# Sheet1.net
KiCad netlist of a schematic drawn in Altium Designer
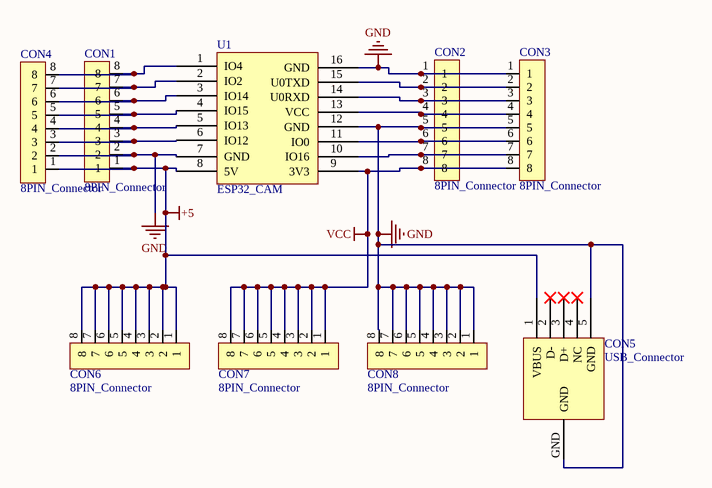
[diagram p0: Sheet1.SchDoc]

(export (version "E")
  (design (tool "Eeschema 10.0.6"))
  (components
    (comp (ref "CON1")
      (value "8PIN_Connector")
      (footprint "8PIN")
      (libsource (lib "") (part "8PIN_Connector_1"))
    )
    (comp (ref "CON2")
      (value "8PIN_Connector")
      (footprint "8PIN")
      (libsource (lib "") (part "8PIN_Connector_2"))
    )
    (comp (ref "CON3")
      (value "8PIN_Connector")
      (footprint "8PIN")
      (libsource (lib "") (part "8PIN_Connector_2"))
    )
    (comp (ref "CON4")
      (value "8PIN_Connector")
      (footprint "8PIN")
      (libsource (lib "") (part "8PIN_Connector_1"))
    )
    (comp (ref "CON5")
      (value "USB_Connector")
      (footprint "MicroUSB")
      (libsource (lib "Mylib") (part "USB_Connector"))
    )
    (comp (ref "CON6")
      (value "8PIN_Connector")
      (footprint "8PIN_2")
      (libsource (lib "Mylib") (part "8PIN_Connector"))
    )
    (comp (ref "CON7")
      (value "8PIN_Connector")
      (footprint "8PIN_2")
      (libsource (lib "Mylib") (part "8PIN_Connector"))
    )
    (comp (ref "CON8")
      (value "8PIN_Connector")
      (footprint "8PIN_2")
      (libsource (lib "Mylib") (part "8PIN_Connector"))
    )
    (comp (ref "U1")
      (value "ESP32_CAM")
      (footprint "ESPCAM_BOARD")
      (libsource (lib "Mylib") (part "ESP32_CAM"))
    )
  )
  (nets
    (net (code "1") (name "+5") (class "Default")
      (node (ref "CON1") (pin "1") (pinfunction "1_1") (pintype "passive"))
      (node (ref "CON4") (pin "1") (pinfunction "1_1") (pintype "passive"))
      (node (ref "CON5") (pin "1") (pinfunction "VBUS_1") (pintype "passive"))
      (node (ref "CON6") (pin "1") (pinfunction "1_1") (pintype "passive"))
      (node (ref "CON6") (pin "2") (pinfunction "2_2") (pintype "passive"))
      (node (ref "CON6") (pin "3") (pinfunction "3_3") (pintype "passive"))
      (node (ref "CON6") (pin "4") (pinfunction "4_4") (pintype "passive"))
      (node (ref "CON6") (pin "5") (pinfunction "5_5") (pintype "passive"))
      (node (ref "CON6") (pin "6") (pinfunction "6_6") (pintype "passive"))
      (node (ref "CON6") (pin "7") (pinfunction "7_7") (pintype "passive"))
      (node (ref "CON6") (pin "8") (pinfunction "8_8") (pintype "passive"))
      (node (ref "U1") (pin "8") (pinfunction "5V_8") (pintype "passive"))
    )
    (net (code "2") (name "GND") (class "Default")
      (node (ref "CON1") (pin "2") (pinfunction "2_2") (pintype "passive"))
      (node (ref "CON2") (pin "1") (pinfunction "1_1") (pintype "passive"))
      (node (ref "CON2") (pin "5") (pinfunction "5_5") (pintype "passive"))
      (node (ref "CON3") (pin "1") (pinfunction "1_1") (pintype "passive"))
      (node (ref "CON3") (pin "5") (pinfunction "5_5") (pintype "passive"))
      (node (ref "CON4") (pin "2") (pinfunction "2_2") (pintype "passive"))
      (node (ref "CON5") (pin "5") (pinfunction "GND_5") (pintype "passive"))
      (node (ref "CON5") (pin "GND") (pinfunction "GND_GND") (pintype "passive"))
      (node (ref "CON8") (pin "1") (pinfunction "1_1") (pintype "passive"))
      (node (ref "CON8") (pin "2") (pinfunction "2_2") (pintype "passive"))
      (node (ref "CON8") (pin "3") (pinfunction "3_3") (pintype "passive"))
      (node (ref "CON8") (pin "4") (pinfunction "4_4") (pintype "passive"))
      (node (ref "CON8") (pin "5") (pinfunction "5_5") (pintype "passive"))
      (node (ref "CON8") (pin "6") (pinfunction "6_6") (pintype "passive"))
      (node (ref "CON8") (pin "7") (pinfunction "7_7") (pintype "passive"))
      (node (ref "CON8") (pin "8") (pinfunction "8_8") (pintype "passive"))
      (node (ref "U1") (pin "12") (pinfunction "GND_12") (pintype "passive"))
      (node (ref "U1") (pin "16") (pinfunction "GND_16") (pintype "passive"))
      (node (ref "U1") (pin "7") (pinfunction "GND_7") (pintype "passive"))
    )
    (net (code "3") (name "Net-(U1-IO0)") (class "Default")
      (node (ref "CON2") (pin "6") (pinfunction "6_6") (pintype "passive"))
      (node (ref "CON3") (pin "6") (pinfunction "6_6") (pintype "passive"))
      (node (ref "U1") (pin "11") (pinfunction "IO0_11") (pintype "passive"))
    )
    (net (code "4") (name "Net-(U1-IO2)") (class "Default")
      (node (ref "CON1") (pin "7") (pinfunction "7_7") (pintype "passive"))
      (node (ref "CON4") (pin "7") (pinfunction "7_7") (pintype "passive"))
      (node (ref "U1") (pin "2") (pinfunction "IO2_2") (pintype "passive"))
    )
    (net (code "5") (name "Net-(U1-IO4)") (class "Default")
      (node (ref "CON1") (pin "8") (pinfunction "8_8") (pintype "passive"))
      (node (ref "CON4") (pin "8") (pinfunction "8_8") (pintype "passive"))
      (node (ref "U1") (pin "1") (pinfunction "IO4_1") (pintype "passive"))
    )
    (net (code "6") (name "Net-(U1-IO12)") (class "Default")
      (node (ref "CON1") (pin "3") (pinfunction "3_3") (pintype "passive"))
      (node (ref "CON4") (pin "3") (pinfunction "3_3") (pintype "passive"))
      (node (ref "U1") (pin "6") (pinfunction "IO12_6") (pintype "passive"))
    )
    (net (code "7") (name "Net-(U1-IO13)") (class "Default")
      (node (ref "CON1") (pin "4") (pinfunction "4_4") (pintype "passive"))
      (node (ref "CON4") (pin "4") (pinfunction "4_4") (pintype "passive"))
      (node (ref "U1") (pin "5") (pinfunction "IO13_5") (pintype "passive"))
    )
    (net (code "8") (name "Net-(U1-IO14)") (class "Default")
      (node (ref "CON1") (pin "6") (pinfunction "6_6") (pintype "passive"))
      (node (ref "CON4") (pin "6") (pinfunction "6_6") (pintype "passive"))
      (node (ref "U1") (pin "3") (pinfunction "IO14_3") (pintype "passive"))
    )
    (net (code "9") (name "Net-(U1-IO15)") (class "Default")
      (node (ref "CON1") (pin "5") (pinfunction "5_5") (pintype "passive"))
      (node (ref "CON4") (pin "5") (pinfunction "5_5") (pintype "passive"))
      (node (ref "U1") (pin "4") (pinfunction "IO15_4") (pintype "passive"))
    )
    (net (code "10") (name "Net-(U1-IO16)") (class "Default")
      (node (ref "CON2") (pin "7") (pinfunction "7_7") (pintype "passive"))
      (node (ref "CON3") (pin "7") (pinfunction "7_7") (pintype "passive"))
      (node (ref "U1") (pin "10") (pinfunction "IO16_10") (pintype "passive"))
    )
    (net (code "11") (name "Net-(U1-U0RXD)") (class "Default")
      (node (ref "CON2") (pin "3") (pinfunction "3_3") (pintype "passive"))
      (node (ref "CON3") (pin "3") (pinfunction "3_3") (pintype "passive"))
      (node (ref "U1") (pin "14") (pinfunction "U0RXD_14") (pintype "passive"))
    )
    (net (code "12") (name "Net-(U1-U0TXD)") (class "Default")
      (node (ref "CON2") (pin "2") (pinfunction "2_2") (pintype "passive"))
      (node (ref "CON3") (pin "2") (pinfunction "2_2") (pintype "passive"))
      (node (ref "U1") (pin "15") (pinfunction "U0TXD_15") (pintype "passive"))
    )
    (net (code "13") (name "Net-(U1-VCC)") (class "Default")
      (node (ref "CON2") (pin "4") (pinfunction "4_4") (pintype "passive"))
      (node (ref "CON3") (pin "4") (pinfunction "4_4") (pintype "passive"))
      (node (ref "U1") (pin "13") (pinfunction "VCC_13") (pintype "passive"))
    )
    (net (code "14") (name "VCC") (class "Default")
      (node (ref "CON2") (pin "8") (pinfunction "8_8") (pintype "passive"))
      (node (ref "CON3") (pin "8") (pinfunction "8_8") (pintype "passive"))
      (node (ref "CON7") (pin "1") (pinfunction "1_1") (pintype "passive"))
      (node (ref "CON7") (pin "2") (pinfunction "2_2") (pintype "passive"))
      (node (ref "CON7") (pin "3") (pinfunction "3_3") (pintype "passive"))
      (node (ref "CON7") (pin "4") (pinfunction "4_4") (pintype "passive"))
      (node (ref "CON7") (pin "5") (pinfunction "5_5") (pintype "passive"))
      (node (ref "CON7") (pin "6") (pinfunction "6_6") (pintype "passive"))
      (node (ref "CON7") (pin "7") (pinfunction "7_7") (pintype "passive"))
      (node (ref "CON7") (pin "8") (pinfunction "8_8") (pintype "passive"))
      (node (ref "U1") (pin "9") (pinfunction "3V3_9") (pintype "passive"))
    )
    (net (code "15") (name "unconnected-(CON5-D+-Pad3)") (class "Default")
      (node (ref "CON5") (pin "3") (pinfunction "D+_3") (pintype "passive+no_connect"))
    )
    (net (code "16") (name "unconnected-(CON5-D--Pad2)") (class "Default")
      (node (ref "CON5") (pin "2") (pinfunction "D-_2") (pintype "passive+no_connect"))
    )
    (net (code "17") (name "unconnected-(CON5-NC-Pad4)") (class "Default")
      (node (ref "CON5") (pin "4") (pinfunction "NC_4") (pintype "passive+no_connect"))
    )
  )
)
